# ain.net
KiCad netlist of a schematic drawn in Altium Designer
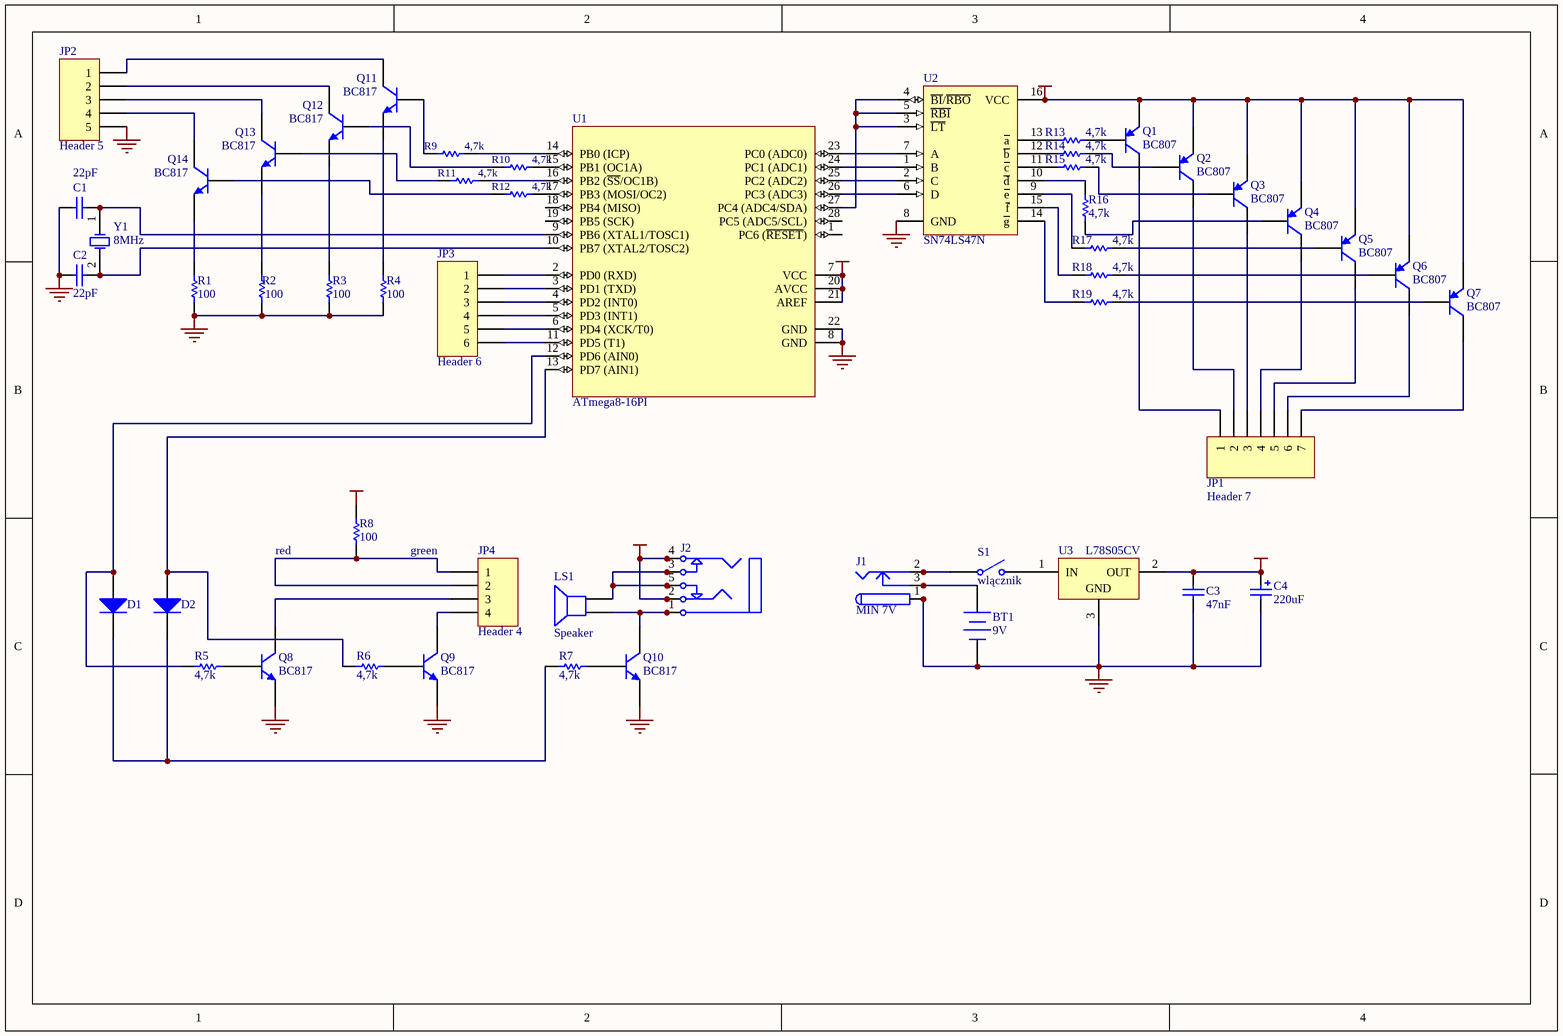
[diagram p0: ain.SchDoc]

(export (version "E")
  (design (tool "Eeschema 10.0.6"))
  (components
    (comp (ref "BT1")
      (value "9V")
      (footprint "BAT-2")
      (description "Multicell Battery")
      (fields (field (name "PUBLISHER") "Altium Limited"))
      (libsource (lib "Miscellaneous Devices") (part "Battery"))
    )
    (comp (ref "C1")
      (value "22pF")
      (footprint "RAD-0.1")
      (description "Capacitor")
      (fields (field (name "Comment") "Cap") (field (name "PUBLISHER") "Altium Limited"))
      (libsource (lib "Miscellaneous Devices") (part "Cap"))
    )
    (comp (ref "C2")
      (value "22pF")
      (footprint "RAD-0.1")
      (description "Capacitor")
      (fields (field (name "Comment") "Cap") (field (name "PUBLISHER") "Altium Limited"))
      (libsource (lib "Miscellaneous Devices") (part "Cap"))
    )
    (comp (ref "C3")
      (value "47nF")
      (footprint "RAD-0.1")
      (description "Capacitor")
      (fields (field (name "Comment") "Cap") (field (name "PUBLISHER") "Altium Limited"))
      (libsource (lib "Miscellaneous Devices") (part "Cap"))
    )
    (comp (ref "C4")
      (value "220uF")
      (footprint "CAPPR2-5X6.8")
      (description "Polarized Capacitor (Radial)")
      (fields (field (name "Comment") "Cap Pol1") (field (name "PUBLISHER") "Altium Limited"))
      (libsource (lib "Miscellaneous Devices") (part "Cap Pol1"))
    )
    (comp (ref "D1")
      (value "Diode")
      (footprint "DSO-C2/X2.3")
      (description "Default Diode")
      (fields (field (name "PUBLISHER") "Altium Limited"))
      (libsource (lib "Miscellaneous Devices") (part "Diode"))
    )
    (comp (ref "D2")
      (value "Diode")
      (footprint "DSO-C2/X2.3")
      (description "Default Diode")
      (fields (field (name "PUBLISHER") "Altium Limited"))
      (libsource (lib "Miscellaneous Devices") (part "Diode"))
    )
    (comp (ref "J1")
      (value "MIN 7V")
      (footprint "KLD-0202")
      (description "Low Voltage Power Supply Connector")
      (fields (field (name "PUBLISHER") "Altium Limited"))
      (libsource (lib "Miscellaneous Connectors") (part "PWR2.5"))
    )
    (comp (ref "J2")
      (value "Phonejack Stereo SW")
      (footprint "Stereo b-jack")
      (description "3-Conductor Jack with 2 break contacts (normals) and 2 auxiliary make contacts")
      (fields (field (name "PUBLISHER") "Altium Limited"))
      (libsource (lib "Miscellaneous Connectors") (part "Phonejack Stereo SW"))
    )
    (comp (ref "JP1")
      (value "Header 7")
      (footprint "HDR1X7")
      (description "Header, 7-Pin")
      (fields (field (name "PUBLISHER") "Altium Limited"))
      (libsource (lib "Miscellaneous Connectors") (part "Header 7"))
    )
    (comp (ref "JP2")
      (value "Header 5")
      (footprint "HDR1X5")
      (description "Header, 5-Pin")
      (fields (field (name "PUBLISHER") "Altium Limited"))
      (libsource (lib "Miscellaneous Connectors") (part "Header 5"))
    )
    (comp (ref "JP3")
      (value "Header 6")
      (footprint "HDR1X6")
      (description "Header, 6-Pin")
      (fields (field (name "PUBLISHER") "Altium Limited"))
      (libsource (lib "Miscellaneous Connectors") (part "Header 6"))
    )
    (comp (ref "JP4")
      (value "Header 4")
      (footprint "HDR1X4")
      (description "Header, 4-Pin")
      (fields (field (name "PUBLISHER") "Altium Limited"))
      (libsource (lib "Miscellaneous Connectors") (part "Header 4"))
    )
    (comp (ref "LS1")
      (value "Speaker")
      (footprint "PIN2")
      (description "Loudspeaker")
      (fields (field (name "PUBLISHER") "Altium Limited"))
      (libsource (lib "Miscellaneous Devices") (part "Speaker"))
    )
    (comp (ref "Q1")
      (value "BC807")
      (footprint "SOT23")
      (description "PNP General-purpose Transistor")
      (fields (field (name "PUBLISHER") "Altium Limited"))
      (libsource (lib "Philips Discrete BJT - Low Power") (part "BC807"))
    )
    (comp (ref "Q2")
      (value "BC807")
      (footprint "SOT23")
      (description "PNP General-purpose Transistor")
      (fields (field (name "PUBLISHER") "Altium Limited"))
      (libsource (lib "Philips Discrete BJT - Low Power") (part "BC807"))
    )
    (comp (ref "Q3")
      (value "BC807")
      (footprint "SOT23")
      (description "PNP General-purpose Transistor")
      (fields (field (name "PUBLISHER") "Altium Limited"))
      (libsource (lib "Philips Discrete BJT - Low Power") (part "BC807"))
    )
    (comp (ref "Q4")
      (value "BC807")
      (footprint "SOT23")
      (description "PNP General-purpose Transistor")
      (fields (field (name "PUBLISHER") "Altium Limited"))
      (libsource (lib "Philips Discrete BJT - Low Power") (part "BC807"))
    )
    (comp (ref "Q5")
      (value "BC807")
      (footprint "SOT23")
      (description "PNP General-purpose Transistor")
      (fields (field (name "PUBLISHER") "Altium Limited"))
      (libsource (lib "Philips Discrete BJT - Low Power") (part "BC807"))
    )
    (comp (ref "Q6")
      (value "BC807")
      (footprint "SOT23")
      (description "PNP General-purpose Transistor")
      (fields (field (name "PUBLISHER") "Altium Limited"))
      (libsource (lib "Philips Discrete BJT - Low Power") (part "BC807"))
    )
    (comp (ref "Q7")
      (value "BC807")
      (footprint "SOT23")
      (description "PNP General-purpose Transistor")
      (fields (field (name "PUBLISHER") "Altium Limited"))
      (libsource (lib "Philips Discrete BJT - Low Power") (part "BC807"))
    )
    (comp (ref "Q8")
      (value "BC817")
      (footprint "SOT23")
      (description "NPN General-purpose Transistor")
      (fields (field (name "PUBLISHER") "Altium Limited"))
      (libsource (lib "Philips Discrete BJT - Low Power") (part "BC817"))
    )
    (comp (ref "Q9")
      (value "BC817")
      (footprint "SOT23")
      (description "NPN General-purpose Transistor")
      (fields (field (name "PUBLISHER") "Altium Limited"))
      (libsource (lib "Philips Discrete BJT - Low Power") (part "BC817"))
    )
    (comp (ref "Q10")
      (value "BC817")
      (footprint "SOT23")
      (description "NPN General-purpose Transistor")
      (fields (field (name "PUBLISHER") "Altium Limited"))
      (libsource (lib "Philips Discrete BJT - Low Power") (part "BC817"))
    )
    (comp (ref "Q11")
      (value "BC817")
      (footprint "SOT23")
      (description "NPN General-purpose Transistor")
      (fields (field (name "PUBLISHER") "Altium Limited"))
      (libsource (lib "") (part "BC817_1"))
    )
    (comp (ref "Q12")
      (value "BC817")
      (footprint "SOT23")
      (description "NPN General-purpose Transistor")
      (fields (field (name "PUBLISHER") "Altium Limited"))
      (libsource (lib "") (part "BC817_1"))
    )
    (comp (ref "Q13")
      (value "BC817")
      (footprint "SOT23")
      (description "NPN General-purpose Transistor")
      (fields (field (name "PUBLISHER") "Altium Limited"))
      (libsource (lib "") (part "BC817_1"))
    )
    (comp (ref "Q14")
      (value "BC817")
      (footprint "SOT23")
      (description "NPN General-purpose Transistor")
      (fields (field (name "PUBLISHER") "Altium Limited"))
      (libsource (lib "") (part "BC817_1"))
    )
    (comp (ref "R1")
      (value "100")
      (footprint "CR2012-0805")
      (description "Resistor")
      (fields (field (name "Comment") "Res1") (field (name "PUBLISHER") "Altium Limited"))
      (libsource (lib "Miscellaneous Devices") (part "Res1"))
    )
    (comp (ref "R2")
      (value "100")
      (footprint "CR2012-0805")
      (description "Resistor")
      (fields (field (name "Comment") "Res1") (field (name "PUBLISHER") "Altium Limited"))
      (libsource (lib "Miscellaneous Devices") (part "Res1"))
    )
    (comp (ref "R3")
      (value "100")
      (footprint "CR2012-0805")
      (description "Resistor")
      (fields (field (name "Comment") "Res1") (field (name "PUBLISHER") "Altium Limited"))
      (libsource (lib "Miscellaneous Devices") (part "Res1"))
    )
    (comp (ref "R4")
      (value "100")
      (footprint "CR2012-0805")
      (description "Resistor")
      (fields (field (name "Comment") "Res1") (field (name "PUBLISHER") "Altium Limited"))
      (libsource (lib "Miscellaneous Devices") (part "Res1"))
    )
    (comp (ref "R5")
      (value "4,7k")
      (footprint "CR2012-0805")
      (description "Resistor")
      (fields (field (name "Comment") "Res1") (field (name "PUBLISHER") "Altium Limited"))
      (libsource (lib "Miscellaneous Devices") (part "Res1"))
    )
    (comp (ref "R6")
      (value "4,7k")
      (footprint "CR2012-0805")
      (description "Resistor")
      (fields (field (name "Comment") "Res1") (field (name "PUBLISHER") "Altium Limited"))
      (libsource (lib "Miscellaneous Devices") (part "Res1"))
    )
    (comp (ref "R7")
      (value "4,7k")
      (footprint "CR2012-0805")
      (description "Resistor")
      (fields (field (name "Comment") "Res1") (field (name "PUBLISHER") "Altium Limited"))
      (libsource (lib "Miscellaneous Devices") (part "Res1"))
    )
    (comp (ref "R8")
      (value "100")
      (footprint "CR2012-0805")
      (description "Resistor")
      (fields (field (name "Comment") "Res1") (field (name "PUBLISHER") "Altium Limited"))
      (libsource (lib "Miscellaneous Devices") (part "Res1"))
    )
    (comp (ref "R9")
      (value "4,7k")
      (footprint "CR2012-0805")
      (description "Resistor")
      (fields (field (name "Comment") "Res1") (field (name "PUBLISHER") "Altium Limited"))
      (libsource (lib "Miscellaneous Devices") (part "Res1"))
    )
    (comp (ref "R10")
      (value "4,7k")
      (footprint "CR2012-0805")
      (description "Resistor")
      (fields (field (name "Comment") "Res1") (field (name "PUBLISHER") "Altium Limited"))
      (libsource (lib "Miscellaneous Devices") (part "Res1"))
    )
    (comp (ref "R11")
      (value "4,7k")
      (footprint "CR2012-0805")
      (description "Resistor")
      (fields (field (name "Comment") "Res1") (field (name "PUBLISHER") "Altium Limited"))
      (libsource (lib "Miscellaneous Devices") (part "Res1"))
    )
    (comp (ref "R12")
      (value "4,7k")
      (footprint "CR2012-0805")
      (description "Resistor")
      (fields (field (name "Comment") "Res1") (field (name "PUBLISHER") "Altium Limited"))
      (libsource (lib "Miscellaneous Devices") (part "Res1"))
    )
    (comp (ref "R13")
      (value "4,7k")
      (footprint "CR2012-0805")
      (description "Resistor")
      (fields (field (name "Comment") "Res1") (field (name "PUBLISHER") "Altium Limited"))
      (libsource (lib "Miscellaneous Devices") (part "Res1"))
    )
    (comp (ref "R14")
      (value "4,7k")
      (footprint "CR2012-0805")
      (description "Resistor")
      (fields (field (name "Comment") "Res1") (field (name "PUBLISHER") "Altium Limited"))
      (libsource (lib "Miscellaneous Devices") (part "Res1"))
    )
    (comp (ref "R15")
      (value "4,7k")
      (footprint "CR2012-0805")
      (description "Resistor")
      (fields (field (name "Comment") "Res1") (field (name "PUBLISHER") "Altium Limited"))
      (libsource (lib "Miscellaneous Devices") (part "Res1"))
    )
    (comp (ref "R16")
      (value "4,7k")
      (footprint "CR2012-0805")
      (description "Resistor")
      (fields (field (name "Comment") "Res1") (field (name "PUBLISHER") "Altium Limited"))
      (libsource (lib "Miscellaneous Devices") (part "Res1"))
    )
    (comp (ref "R17")
      (value "4,7k")
      (footprint "CR2012-0805")
      (description "Resistor")
      (fields (field (name "Comment") "Res1") (field (name "PUBLISHER") "Altium Limited"))
      (libsource (lib "Miscellaneous Devices") (part "Res1"))
    )
    (comp (ref "R18")
      (value "4,7k")
      (footprint "CR2012-0805")
      (description "Resistor")
      (fields (field (name "Comment") "Res1") (field (name "PUBLISHER") "Altium Limited"))
      (libsource (lib "Miscellaneous Devices") (part "Res1"))
    )
    (comp (ref "R19")
      (value "4,7k")
      (footprint "CR2012-0805")
      (description "Resistor")
      (fields (field (name "Comment") "Res1") (field (name "PUBLISHER") "Altium Limited"))
      (libsource (lib "Miscellaneous Devices") (part "Res1"))
    )
    (comp (ref "S1")
      (value "wlącznik")
      (footprint "SPST-2")
      (description "Single-Pole, Single-Throw Switch")
      (fields (field (name "PUBLISHER") "Altium Limited"))
      (libsource (lib "Miscellaneous Devices") (part "SW-SPST"))
    )
    (comp (ref "U1")
      (value "ATmega8-16PI")
      (footprint "28P3")
      (description "8-Bit AVR Microcontroller with 8K Bytes of In-System Programmable Flash Memory")
      (fields (field (name "PUBLISHER") "Altium Limited"))
      (libsource (lib "Atmel Microcontroller 8-Bit AVR") (part "ATmega8-16PI"))
    )
    (comp (ref "U2")
      (value "SN74LS47N")
      (footprint "N016")
      (description "BCD-to-Seven-Segment Decoder/Driver")
      (fields (field (name "PUBLISHER") "Altium Limited"))
      (libsource (lib "TI Interface Display Driver") (part "SN74LS47N"))
    )
    (comp (ref "U3")
      (value "L78S05CV")
      (footprint "TO220VW")
      (description "2A Positive Voltage Regulator")
      (fields (field (name "PUBLISHER") "Altium Limited"))
      (libsource (lib "ST Power Mgt Voltage Regulator") (part "L78S05CV"))
    )
    (comp (ref "Y1")
      (value "8MHz")
      (footprint "RAD-0.2")
      (description "Crystal Oscillator")
      (fields (field (name "PUBLISHER") "Altium Limited"))
      (libsource (lib "Miscellaneous Devices") (part "XTAL"))
    )
  )
  (nets
    (net (code "1") (name "GND") (class "Default")
      (node (ref "BT1") (pin "2") (pinfunction "-_2") (pintype "passive"))
      (node (ref "C1") (pin "1") (pinfunction "1_1") (pintype "passive"))
      (node (ref "C2") (pin "1") (pinfunction "1_1") (pintype "passive"))
      (node (ref "C3") (pin "1") (pinfunction "1_1") (pintype "passive"))
      (node (ref "C4") (pin "2") (pinfunction "2_2") (pintype "passive"))
      (node (ref "J1") (pin "1") (pintype "power_in"))
      (node (ref "J1") (pin "1A") (pintype "power_in"))
      (node (ref "J1") (pin "1B") (pintype "power_in"))
      (node (ref "JP2") (pin "5") (pinfunction "5_5") (pintype "passive"))
      (node (ref "Q10") (pin "2") (pinfunction "E_2") (pintype "passive"))
      (node (ref "Q8") (pin "2") (pinfunction "E_2") (pintype "passive"))
      (node (ref "Q9") (pin "2") (pinfunction "E_2") (pintype "passive"))
      (node (ref "R1") (pin "1") (pinfunction "1_1") (pintype "passive"))
      (node (ref "R2") (pin "1") (pinfunction "1_1") (pintype "passive"))
      (node (ref "R3") (pin "1") (pinfunction "1_1") (pintype "passive"))
      (node (ref "R4") (pin "1") (pinfunction "1_1") (pintype "passive"))
      (node (ref "U1") (pin "22") (pinfunction "GND_22") (pintype "power_in"))
      (node (ref "U1") (pin "8") (pinfunction "GND_8") (pintype "power_in"))
      (node (ref "U2") (pin "8") (pinfunction "GND_8") (pintype "power_in"))
      (node (ref "U3") (pin "3") (pinfunction "GND_3") (pintype "power_in"))
    )
    (net (code "2") (name "Net-(BT1-+)") (class "Default")
      (node (ref "BT1") (pin "1") (pinfunction "+_1") (pintype "passive"))
      (node (ref "J1") (pin "3") (pintype "power_in"))
      (node (ref "J1") (pin "3A") (pintype "power_in"))
      (node (ref "J1") (pin "3B") (pintype "power_in"))
    )
    (net (code "3") (name "Net-(D1-A)") (class "Default")
      (node (ref "D1") (pin "1") (pinfunction "A_1") (pintype "passive"))
      (node (ref "R5") (pin "1") (pinfunction "1_1") (pintype "passive"))
      (node (ref "U1") (pin "12") (pinfunction "PD6_(AIN0)_12") (pintype "bidirectional"))
    )
    (net (code "4") (name "Net-(D1-K)") (class "Default")
      (node (ref "D1") (pin "2") (pinfunction "K_2") (pintype "passive"))
      (node (ref "D2") (pin "2") (pinfunction "K_2") (pintype "passive"))
      (node (ref "R7") (pin "1") (pinfunction "1_1") (pintype "passive"))
    )
    (net (code "5") (name "Net-(D2-A)") (class "Default")
      (node (ref "D2") (pin "1") (pinfunction "A_1") (pintype "passive"))
      (node (ref "R6") (pin "1") (pinfunction "1_1") (pintype "passive"))
      (node (ref "U1") (pin "13") (pinfunction "PD7_(AIN1)_13") (pintype "bidirectional"))
    )
    (net (code "6") (name "Net-(J2-Pad3)") (class "Default")
      (node (ref "J2") (pin "3") (pintype "passive"))
      (node (ref "J2") (pin "3A") (pintype "passive"))
      (node (ref "J2") (pin "3B") (pintype "passive"))
      (node (ref "J2") (pin "5") (pintype "passive"))
      (node (ref "J2") (pin "5A") (pintype "passive"))
      (node (ref "J2") (pin "5B") (pintype "passive"))
      (node (ref "LS1") (pin "1") (pinfunction "1_1") (pintype "passive"))
    )
    (net (code "7") (name "Net-(JP4-Pad1)") (class "Default")
      (node (ref "JP4") (pin "1") (pinfunction "1_1") (pintype "passive"))
      (node (ref "JP4") (pin "2") (pinfunction "2_2") (pintype "passive"))
      (node (ref "R8") (pin "1") (pinfunction "1_1") (pintype "passive"))
    )
    (net (code "8") (name "Net-(Q1-B)") (class "Default")
      (node (ref "Q1") (pin "1") (pinfunction "B_1") (pintype "passive"))
      (node (ref "R13") (pin "2") (pinfunction "2_2") (pintype "passive"))
    )
    (net (code "9") (name "Net-(Q1-C)") (class "Default")
      (node (ref "JP1") (pin "1") (pinfunction "1_1") (pintype "passive"))
      (node (ref "Q1") (pin "3") (pinfunction "C_3") (pintype "passive"))
    )
    (net (code "10") (name "Net-(Q2-B)") (class "Default")
      (node (ref "Q2") (pin "1") (pinfunction "B_1") (pintype "passive"))
      (node (ref "R14") (pin "2") (pinfunction "2_2") (pintype "passive"))
    )
    (net (code "11") (name "Net-(Q2-C)") (class "Default")
      (node (ref "JP1") (pin "2") (pinfunction "2_2") (pintype "passive"))
      (node (ref "Q2") (pin "3") (pinfunction "C_3") (pintype "passive"))
    )
    (net (code "12") (name "Net-(Q3-B)") (class "Default")
      (node (ref "Q3") (pin "1") (pinfunction "B_1") (pintype "passive"))
      (node (ref "R15") (pin "2") (pinfunction "2_2") (pintype "passive"))
    )
    (net (code "13") (name "Net-(Q3-C)") (class "Default")
      (node (ref "JP1") (pin "3") (pinfunction "3_3") (pintype "passive"))
      (node (ref "Q3") (pin "3") (pinfunction "C_3") (pintype "passive"))
    )
    (net (code "14") (name "Net-(Q4-B)") (class "Default")
      (node (ref "Q4") (pin "1") (pinfunction "B_1") (pintype "passive"))
      (node (ref "R16") (pin "2") (pinfunction "2_2") (pintype "passive"))
    )
    (net (code "15") (name "Net-(Q4-C)") (class "Default")
      (node (ref "JP1") (pin "4") (pinfunction "4_4") (pintype "passive"))
      (node (ref "Q4") (pin "3") (pinfunction "C_3") (pintype "passive"))
    )
    (net (code "16") (name "Net-(Q5-B)") (class "Default")
      (node (ref "Q5") (pin "1") (pinfunction "B_1") (pintype "passive"))
      (node (ref "R17") (pin "2") (pinfunction "2_2") (pintype "passive"))
    )
    (net (code "17") (name "Net-(Q5-C)") (class "Default")
      (node (ref "JP1") (pin "5") (pinfunction "5_5") (pintype "passive"))
      (node (ref "Q5") (pin "3") (pinfunction "C_3") (pintype "passive"))
    )
    (net (code "18") (name "Net-(Q6-B)") (class "Default")
      (node (ref "Q6") (pin "1") (pinfunction "B_1") (pintype "passive"))
      (node (ref "R18") (pin "2") (pinfunction "2_2") (pintype "passive"))
    )
    (net (code "19") (name "Net-(Q6-C)") (class "Default")
      (node (ref "JP1") (pin "6") (pinfunction "6_6") (pintype "passive"))
      (node (ref "Q6") (pin "3") (pinfunction "C_3") (pintype "passive"))
    )
    (net (code "20") (name "Net-(Q7-B)") (class "Default")
      (node (ref "Q7") (pin "1") (pinfunction "B_1") (pintype "passive"))
      (node (ref "R19") (pin "2") (pinfunction "2_2") (pintype "passive"))
    )
    (net (code "21") (name "Net-(Q7-C)") (class "Default")
      (node (ref "JP1") (pin "7") (pinfunction "7_7") (pintype "passive"))
      (node (ref "Q7") (pin "3") (pinfunction "C_3") (pintype "passive"))
    )
    (net (code "22") (name "Net-(Q8-B)") (class "Default")
      (node (ref "Q8") (pin "1") (pinfunction "B_1") (pintype "passive"))
      (node (ref "R5") (pin "2") (pinfunction "2_2") (pintype "passive"))
    )
    (net (code "23") (name "Net-(Q8-C)") (class "Default")
      (node (ref "JP4") (pin "3") (pinfunction "3_3") (pintype "passive"))
      (node (ref "Q8") (pin "3") (pinfunction "C_3") (pintype "passive"))
    )
    (net (code "24") (name "Net-(Q9-B)") (class "Default")
      (node (ref "Q9") (pin "1") (pinfunction "B_1") (pintype "passive"))
      (node (ref "R6") (pin "2") (pinfunction "2_2") (pintype "passive"))
    )
    (net (code "25") (name "Net-(Q9-C)") (class "Default")
      (node (ref "JP4") (pin "4") (pinfunction "4_4") (pintype "passive"))
      (node (ref "Q9") (pin "3") (pinfunction "C_3") (pintype "passive"))
    )
    (net (code "26") (name "Net-(Q10-B)") (class "Default")
      (node (ref "Q10") (pin "1") (pinfunction "B_1") (pintype "passive"))
      (node (ref "R7") (pin "2") (pinfunction "2_2") (pintype "passive"))
    )
    (net (code "27") (name "Net-(Q10-C)") (class "Default")
      (node (ref "J2") (pin "1") (pintype "passive"))
      (node (ref "J2") (pin "1A") (pintype "passive"))
      (node (ref "J2") (pin "1B") (pintype "passive"))
      (node (ref "LS1") (pin "2") (pinfunction "2_2") (pintype "passive"))
      (node (ref "Q10") (pin "3") (pinfunction "C_3") (pintype "passive"))
    )
    (net (code "28") (name "Net-(Q11-B)") (class "Default")
      (node (ref "Q11") (pin "1") (pinfunction "B_1") (pintype "passive"))
      (node (ref "R9") (pin "1") (pinfunction "1_1") (pintype "passive"))
    )
    (net (code "29") (name "Net-(Q11-C)") (class "Default")
      (node (ref "JP2") (pin "1") (pinfunction "1_1") (pintype "passive"))
      (node (ref "Q11") (pin "3") (pinfunction "C_3") (pintype "passive"))
    )
    (net (code "30") (name "Net-(Q11-E)") (class "Default")
      (node (ref "Q11") (pin "2") (pinfunction "E_2") (pintype "passive"))
      (node (ref "R4") (pin "2") (pinfunction "2_2") (pintype "passive"))
    )
    (net (code "31") (name "Net-(Q12-B)") (class "Default")
      (node (ref "Q12") (pin "1") (pinfunction "B_1") (pintype "passive"))
      (node (ref "R10") (pin "1") (pinfunction "1_1") (pintype "passive"))
    )
    (net (code "32") (name "Net-(Q12-C)") (class "Default")
      (node (ref "JP2") (pin "2") (pinfunction "2_2") (pintype "passive"))
      (node (ref "Q12") (pin "3") (pinfunction "C_3") (pintype "passive"))
    )
    (net (code "33") (name "Net-(Q12-E)") (class "Default")
      (node (ref "Q12") (pin "2") (pinfunction "E_2") (pintype "passive"))
      (node (ref "R3") (pin "2") (pinfunction "2_2") (pintype "passive"))
    )
    (net (code "34") (name "Net-(Q13-B)") (class "Default")
      (node (ref "Q13") (pin "1") (pinfunction "B_1") (pintype "passive"))
      (node (ref "R11") (pin "1") (pinfunction "1_1") (pintype "passive"))
    )
    (net (code "35") (name "Net-(Q13-C)") (class "Default")
      (node (ref "JP2") (pin "3") (pinfunction "3_3") (pintype "passive"))
      (node (ref "Q13") (pin "3") (pinfunction "C_3") (pintype "passive"))
    )
    (net (code "36") (name "Net-(Q13-E)") (class "Default")
      (node (ref "Q13") (pin "2") (pinfunction "E_2") (pintype "passive"))
      (node (ref "R2") (pin "2") (pinfunction "2_2") (pintype "passive"))
    )
    (net (code "37") (name "Net-(Q14-B)") (class "Default")
      (node (ref "Q14") (pin "1") (pinfunction "B_1") (pintype "passive"))
      (node (ref "R12") (pin "1") (pinfunction "1_1") (pintype "passive"))
    )
    (net (code "38") (name "Net-(Q14-C)") (class "Default")
      (node (ref "JP2") (pin "4") (pinfunction "4_4") (pintype "passive"))
      (node (ref "Q14") (pin "3") (pinfunction "C_3") (pintype "passive"))
    )
    (net (code "39") (name "Net-(Q14-E)") (class "Default")
      (node (ref "Q14") (pin "2") (pinfunction "E_2") (pintype "passive"))
      (node (ref "R1") (pin "2") (pinfunction "2_2") (pintype "passive"))
    )
    (net (code "40") (name "Net-(S1-COMMON)") (class "Default")
      (node (ref "J1") (pin "2") (pintype "power_in"))
      (node (ref "J1") (pin "2A") (pintype "power_in"))
      (node (ref "J1") (pin "2B") (pintype "power_in"))
      (node (ref "S1") (pin "1") (pinfunction "COMMON_1") (pintype "passive"))
    )
    (net (code "41") (name "Net-(S1-NO)") (class "Default")
      (node (ref "S1") (pin "2") (pinfunction "NO_2") (pintype "passive"))
      (node (ref "U3") (pin "1") (pinfunction "IN_1") (pintype "power_in"))
    )
    (net (code "42") (name "Net-(U1-PB0_(ICP))") (class "Default")
      (node (ref "R9") (pin "2") (pinfunction "2_2") (pintype "passive"))
      (node (ref "U1") (pin "14") (pinfunction "PB0_(ICP)_14") (pintype "bidirectional"))
    )
    (net (code "43") (name "Net-(U1-PB1_(OC1A))") (class "Default")
      (node (ref "R10") (pin "2") (pinfunction "2_2") (pintype "passive"))
      (node (ref "U1") (pin "15") (pinfunction "PB1_(OC1A)_15") (pintype "bidirectional"))
    )
    (net (code "44") (name "Net-(U1-PB2_(~{SS}{slash}OC1B))") (class "Default")
      (node (ref "R11") (pin "2") (pinfunction "2_2") (pintype "passive"))
      (node (ref "U1") (pin "16") (pinfunction "PB2_(~{SS}/OC1B)_16") (pintype "bidirectional"))
    )
    (net (code "45") (name "Net-(U1-PB3_(MOSI{slash}OC2))") (class "Default")
      (node (ref "R12") (pin "2") (pinfunction "2_2") (pintype "passive"))
      (node (ref "U1") (pin "17") (pinfunction "PB3_(MOSI/OC2)_17") (pintype "bidirectional"))
    )
    (net (code "46") (name "Net-(U1-PB6_(XTAL1{slash}TOSC1))") (class "Default")
      (node (ref "C1") (pin "2") (pinfunction "2_2") (pintype "passive"))
      (node (ref "U1") (pin "9") (pinfunction "PB6_(XTAL1/TOSC1)_9") (pintype "bidirectional"))
      (node (ref "Y1") (pin "1") (pinfunction "OSC1_1") (pintype "passive"))
    )
    (net (code "47") (name "Net-(U1-PB7_(XTAL2{slash}TOSC2))") (class "Default")
      (node (ref "C2") (pin "2") (pinfunction "2_2") (pintype "passive"))
      (node (ref "U1") (pin "10") (pinfunction "PB7_(XTAL2/TOSC2)_10") (pintype "bidirectional"))
      (node (ref "Y1") (pin "2") (pinfunction "OSC2_2") (pintype "passive"))
    )
    (net (code "48") (name "Net-(U1-PC0_(ADC0))") (class "Default")
      (node (ref "U1") (pin "23") (pinfunction "PC0_(ADC0)_23") (pintype "bidirectional"))
      (node (ref "U2") (pin "7") (pinfunction "A_7") (pintype "input"))
    )
    (net (code "49") (name "Net-(U1-PC1_(ADC1))") (class "Default")
      (node (ref "U1") (pin "24") (pinfunction "PC1_(ADC1)_24") (pintype "bidirectional"))
      (node (ref "U2") (pin "1") (pinfunction "B_1") (pintype "input"))
    )
    (net (code "50") (name "Net-(U1-PC2_(ADC2))") (class "Default")
      (node (ref "U1") (pin "25") (pinfunction "PC2_(ADC2)_25") (pintype "bidirectional"))
      (node (ref "U2") (pin "2") (pinfunction "C_2") (pintype "input"))
    )
    (net (code "51") (name "Net-(U1-PC3_(ADC3))") (class "Default")
      (node (ref "U1") (pin "26") (pinfunction "PC3_(ADC3)_26") (pintype "bidirectional"))
      (node (ref "U2") (pin "6") (pinfunction "D_6") (pintype "input"))
    )
    (net (code "52") (name "Net-(U1-PC4_(ADC4{slash}SDA))") (class "Default")
      (node (ref "U1") (pin "27") (pinfunction "PC4_(ADC4/SDA)_27") (pintype "bidirectional"))
      (node (ref "U2") (pin "3") (pinfunction "~{LT}_3") (pintype "input"))
      (node (ref "U2") (pin "4") (pinfunction "~{BI}/~{RBO}_4") (pintype "bidirectional"))
      (node (ref "U2") (pin "5") (pinfunction "~{RBI}_5") (pintype "input"))
    )
    (net (code "53") (name "Net-(U1-PD0_(RXD))") (class "Default")
      (node (ref "JP3") (pin "1") (pinfunction "1_1") (pintype "passive"))
      (node (ref "U1") (pin "2") (pinfunction "PD0_(RXD)_2") (pintype "bidirectional"))
    )
    (net (code "54") (name "Net-(U1-PD1_(TXD))") (class "Default")
      (node (ref "JP3") (pin "2") (pinfunction "2_2") (pintype "passive"))
      (node (ref "U1") (pin "3") (pinfunction "PD1_(TXD)_3") (pintype "bidirectional"))
    )
    (net (code "55") (name "Net-(U1-PD2_(INT0))") (class "Default")
      (node (ref "JP3") (pin "3") (pinfunction "3_3") (pintype "passive"))
      (node (ref "U1") (pin "4") (pinfunction "PD2_(INT0)_4") (pintype "bidirectional"))
    )
    (net (code "56") (name "Net-(U1-PD3_(INT1))") (class "Default")
      (node (ref "JP3") (pin "4") (pinfunction "4_4") (pintype "passive"))
      (node (ref "U1") (pin "5") (pinfunction "PD3_(INT1)_5") (pintype "bidirectional"))
    )
    (net (code "57") (name "Net-(U1-PD4_(XCK{slash}T0))") (class "Default")
      (node (ref "JP3") (pin "5") (pinfunction "5_5") (pintype "passive"))
      (node (ref "U1") (pin "6") (pinfunction "PD4_(XCK/T0)_6") (pintype "bidirectional"))
    )
    (net (code "58") (name "Net-(U1-PD5_(T1))") (class "Default")
      (node (ref "JP3") (pin "6") (pinfunction "6_6") (pintype "passive"))
      (node (ref "U1") (pin "11") (pinfunction "PD5_(T1)_11") (pintype "bidirectional"))
    )
    (net (code "59") (name "Net-(U2-~{a})") (class "Default")
      (node (ref "R13") (pin "1") (pinfunction "1_1") (pintype "passive"))
      (node (ref "U2") (pin "13") (pinfunction "~{a}_13") (pintype "open_collector"))
    )
    (net (code "60") (name "Net-(U2-~{b})") (class "Default")
      (node (ref "R14") (pin "1") (pinfunction "1_1") (pintype "passive"))
      (node (ref "U2") (pin "12") (pinfunction "~{b}_12") (pintype "open_collector"))
    )
    (net (code "61") (name "Net-(U2-~{c})") (class "Default")
      (node (ref "R15") (pin "1") (pinfunction "1_1") (pintype "passive"))
      (node (ref "U2") (pin "11") (pinfunction "~{c}_11") (pintype "open_collector"))
    )
    (net (code "62") (name "Net-(U2-~{d})") (class "Default")
      (node (ref "R16") (pin "1") (pinfunction "1_1") (pintype "passive"))
      (node (ref "U2") (pin "10") (pinfunction "~{d}_10") (pintype "open_collector"))
    )
    (net (code "63") (name "Net-(U2-~{e})") (class "Default")
      (node (ref "R17") (pin "1") (pinfunction "1_1") (pintype "passive"))
      (node (ref "U2") (pin "9") (pinfunction "~{e}_9") (pintype "open_collector"))
    )
    (net (code "64") (name "Net-(U2-~{f})") (class "Default")
      (node (ref "R18") (pin "1") (pinfunction "1_1") (pintype "passive"))
      (node (ref "U2") (pin "15") (pinfunction "~{f}_15") (pintype "open_collector"))
    )
    (net (code "65") (name "Net-(U2-~{g})") (class "Default")
      (node (ref "R19") (pin "1") (pinfunction "1_1") (pintype "passive"))
      (node (ref "U2") (pin "14") (pinfunction "~{g}_14") (pintype "open_collector"))
    )
    (net (code "66") (name "VCC") (class "Default")
      (node (ref "C3") (pin "2") (pinfunction "2_2") (pintype "passive"))
      (node (ref "C4") (pin "1") (pinfunction "1_1") (pintype "passive"))
      (node (ref "J2") (pin "2") (pintype "passive"))
      (node (ref "J2") (pin "2A") (pintype "passive"))
      (node (ref "J2") (pin "2B") (pintype "passive"))
      (node (ref "J2") (pin "4") (pintype "passive"))
      (node (ref "J2") (pin "4A") (pintype "passive"))
      (node (ref "J2") (pin "4B") (pintype "passive"))
      (node (ref "Q1") (pin "2") (pinfunction "E_2") (pintype "passive"))
      (node (ref "Q2") (pin "2") (pinfunction "E_2") (pintype "passive"))
      (node (ref "Q3") (pin "2") (pinfunction "E_2") (pintype "passive"))
      (node (ref "Q4") (pin "2") (pinfunction "E_2") (pintype "passive"))
      (node (ref "Q5") (pin "2") (pinfunction "E_2") (pintype "passive"))
      (node (ref "Q6") (pin "2") (pinfunction "E_2") (pintype "passive"))
      (node (ref "Q7") (pin "2") (pinfunction "E_2") (pintype "passive"))
      (node (ref "R8") (pin "2") (pinfunction "2_2") (pintype "passive"))
      (node (ref "U1") (pin "20") (pinfunction "AVCC_20") (pintype "power_in"))
      (node (ref "U1") (pin "21") (pinfunction "AREF_21") (pintype "passive"))
      (node (ref "U1") (pin "7") (pinfunction "VCC_7") (pintype "power_in"))
      (node (ref "U2") (pin "16") (pinfunction "VCC_16") (pintype "power_in"))
      (node (ref "U3") (pin "2") (pinfunction "OUT_2") (pintype "power_in"))
    )
    (net (code "67") (name "unconnected-(U1-PB4_(MISO)-Pad18)") (class "Default")
      (node (ref "U1") (pin "18") (pinfunction "PB4_(MISO)_18") (pintype "bidirectional"))
    )
    (net (code "68") (name "unconnected-(U1-PB5_(SCK)-Pad19)") (class "Default")
      (node (ref "U1") (pin "19") (pinfunction "PB5_(SCK)_19") (pintype "bidirectional"))
    )
    (net (code "69") (name "unconnected-(U1-PC5_(ADC5{slash}SCL)-Pad28)") (class "Default")
      (node (ref "U1") (pin "28") (pinfunction "PC5_(ADC5/SCL)_28") (pintype "bidirectional"))
    )
    (net (code "70") (name "unconnected-(U1-PC6_(~{RESET})-Pad1)") (class "Default")
      (node (ref "U1") (pin "1") (pinfunction "PC6_(~{RESET})_1") (pintype "bidirectional"))
    )
  )
)
